# LF_HF_ant.net
KiCad netlist of a schematic drawn in EAGLE
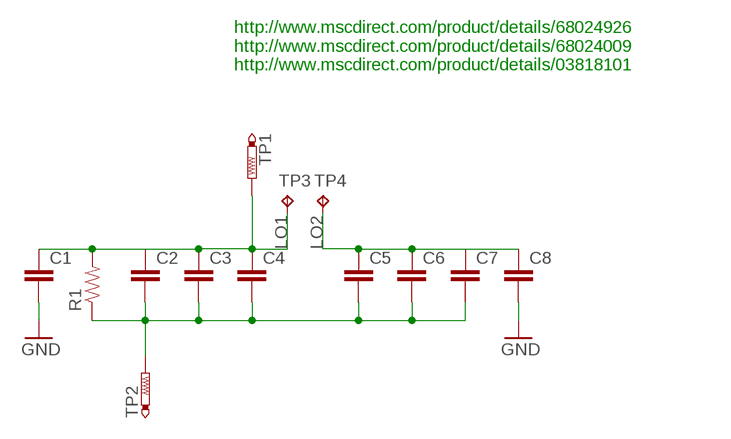
[diagram p0: schematic, sheet 1]
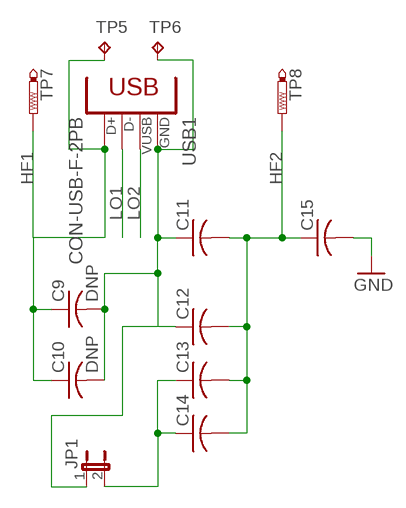
[diagram p1: schematic, sheet 2]

(export (version "E")
  (design (tool "Eeschema 10.0.6"))
  (components
    (comp (ref "C9")
      (value "DNP")
      (footprint "eagle-import:C1206")
      (libsource (lib "eagle-import") (part "C-USC1206"))
    )
    (comp (ref "C10")
      (value "DNP")
      (footprint "eagle-import:C1206")
      (libsource (lib "eagle-import") (part "C-USC1206"))
    )
    (comp (ref "C11")
      (value "C-USC1206")
      (footprint "eagle-import:C1206")
      (libsource (lib "eagle-import") (part "C-USC1206"))
    )
    (comp (ref "C12")
      (value "C-USC1206")
      (footprint "eagle-import:C1206")
      (libsource (lib "eagle-import") (part "C-USC1206"))
    )
    (comp (ref "C13")
      (value "C-USC1206")
      (footprint "eagle-import:C1206")
      (libsource (lib "eagle-import") (part "C-USC1206"))
    )
    (comp (ref "C14")
      (value "C-USC1206")
      (footprint "eagle-import:C1206")
      (libsource (lib "eagle-import") (part "C-USC1206"))
    )
    (comp (ref "C15")
      (value "C-USC1206")
      (footprint "eagle-import:C1206")
      (libsource (lib "eagle-import") (part "C-USC1206"))
    )
    (comp (ref "JP1")
      (value "JUMPER-2SMD-NO")
      (footprint "eagle-import:SJ_2S-NO")
      (libsource (lib "eagle-import") (part "JUMPER-2SMD-NO"))
    )
    (comp (ref "TP5")
      (value "TP")
      (footprint "eagle-import:TP_MILLMAX_R")
      (libsource (lib "eagle-import") (part "TP"))
    )
    (comp (ref "TP6")
      (value "TP")
      (footprint "eagle-import:TP_MILLMAX_R")
      (libsource (lib "eagle-import") (part "TP"))
    )
    (comp (ref "TP7")
      (value "PTR1PAD1-17")
      (footprint "eagle-import:P1-17")
      (libsource (lib "eagle-import") (part "PTR1PAD1-17"))
    )
    (comp (ref "TP8")
      (value "PTR1PAD1-17")
      (footprint "eagle-import:P1-17")
      (libsource (lib "eagle-import") (part "PTR1PAD1-17"))
    )
    (comp (ref "USB1")
      (value "CON-USB-F-2PB")
      (footprint "eagle-import:CONN_USB_A_F")
      (libsource (lib "eagle-import") (part "CON-USB-F-2PB"))
    )
    (comp (ref "C1")
      (value "CAP1206")
      (footprint "eagle-import:1206")
      (libsource (lib "eagle-import") (part "CAP1206"))
    )
    (comp (ref "C2")
      (value "CAP1206")
      (footprint "eagle-import:1206")
      (libsource (lib "eagle-import") (part "CAP1206"))
    )
    (comp (ref "C3")
      (value "CAP1206")
      (footprint "eagle-import:1206")
      (libsource (lib "eagle-import") (part "CAP1206"))
    )
    (comp (ref "C4")
      (value "CAP1206")
      (footprint "eagle-import:1206")
      (libsource (lib "eagle-import") (part "CAP1206"))
    )
    (comp (ref "C5")
      (value "CAP1206")
      (footprint "eagle-import:1206")
      (libsource (lib "eagle-import") (part "CAP1206"))
    )
    (comp (ref "C6")
      (value "CAP1206")
      (footprint "eagle-import:1206")
      (libsource (lib "eagle-import") (part "CAP1206"))
    )
    (comp (ref "C7")
      (value "CAP1206")
      (footprint "eagle-import:1206")
      (libsource (lib "eagle-import") (part "CAP1206"))
    )
    (comp (ref "C8")
      (value "CAP1206")
      (footprint "eagle-import:1206")
      (libsource (lib "eagle-import") (part "CAP1206"))
    )
    (comp (ref "R1")
      (value "RESISTOR0603-RES")
      (footprint "eagle-import:0603-RES")
      (libsource (lib "eagle-import") (part "RESISTOR0603-RES"))
    )
    (comp (ref "TP1")
      (value "PTR1PAD1-17")
      (footprint "eagle-import:P1-17")
      (libsource (lib "eagle-import") (part "PTR1PAD1-17"))
    )
    (comp (ref "TP2")
      (value "PTR1PAD1-17")
      (footprint "eagle-import:P1-17")
      (libsource (lib "eagle-import") (part "PTR1PAD1-17"))
    )
    (comp (ref "TP3")
      (value "TP")
      (footprint "eagle-import:TP_MILLMAX_R")
      (libsource (lib "eagle-import") (part "TP"))
    )
    (comp (ref "TP4")
      (value "TP")
      (footprint "eagle-import:TP_MILLMAX_R")
      (libsource (lib "eagle-import") (part "TP"))
    )
  )
  (nets
    (net (code "1") (name "GND") (class "Default")
      (node (ref "C1") (pin "2") (pinfunction "2_2") (pintype "passive"))
      (node (ref "C15") (pin "2") (pinfunction "2_2") (pintype "passive"))
      (node (ref "C8") (pin "2") (pinfunction "2_2") (pintype "passive"))
    )
    (net (code "2") (name "HF1") (class "Default")
      (node (ref "C10") (pin "1") (pinfunction "1_1") (pintype "passive"))
      (node (ref "C9") (pin "1") (pinfunction "1_1") (pintype "passive"))
      (node (ref "TP5") (pin "TP") (pinfunction "TP_TP") (pintype "input"))
      (node (ref "TP7") (pin "TP") (pinfunction "TP_TP") (pintype "input"))
      (node (ref "USB1") (pin "3") (pinfunction "D+_3") (pintype "bidirectional"))
    )
    (net (code "3") (name "HF2") (class "Default")
      (node (ref "C11") (pin "2") (pinfunction "2_2") (pintype "passive"))
      (node (ref "C12") (pin "2") (pinfunction "2_2") (pintype "passive"))
      (node (ref "C13") (pin "2") (pinfunction "2_2") (pintype "passive"))
      (node (ref "C14") (pin "2") (pinfunction "2_2") (pintype "passive"))
      (node (ref "C15") (pin "1") (pinfunction "1_1") (pintype "passive"))
      (node (ref "TP8") (pin "TP") (pinfunction "TP_TP") (pintype "input"))
    )
    (net (code "4") (name "LO1") (class "Default")
      (node (ref "C1") (pin "1") (pinfunction "1_1") (pintype "passive"))
      (node (ref "C2") (pin "1") (pinfunction "1_1") (pintype "passive"))
      (node (ref "C3") (pin "1") (pinfunction "1_1") (pintype "passive"))
      (node (ref "C4") (pin "1") (pinfunction "1_1") (pintype "passive"))
      (node (ref "R1") (pin "2") (pinfunction "2_2") (pintype "passive"))
      (node (ref "TP1") (pin "TP") (pinfunction "TP_TP") (pintype "input"))
      (node (ref "TP3") (pin "TP") (pinfunction "TP_TP") (pintype "input"))
      (node (ref "USB1") (pin "2") (pinfunction "D-_2") (pintype "bidirectional"))
    )
    (net (code "5") (name "LO2") (class "Default")
      (node (ref "C5") (pin "1") (pinfunction "1_1") (pintype "passive"))
      (node (ref "C6") (pin "1") (pinfunction "1_1") (pintype "passive"))
      (node (ref "C7") (pin "1") (pinfunction "1_1") (pintype "passive"))
      (node (ref "C8") (pin "1") (pinfunction "1_1") (pintype "passive"))
      (node (ref "TP4") (pin "TP") (pinfunction "TP_TP") (pintype "input"))
      (node (ref "USB1") (pin "1") (pinfunction "VUSB_1") (pintype "bidirectional"))
    )
    (net (code "6") (name "Net-(C2-Pad2)") (class "Default")
      (node (ref "C2") (pin "2") (pinfunction "2_2") (pintype "passive"))
      (node (ref "C3") (pin "2") (pinfunction "2_2") (pintype "passive"))
      (node (ref "C4") (pin "2") (pinfunction "2_2") (pintype "passive"))
      (node (ref "C5") (pin "2") (pinfunction "2_2") (pintype "passive"))
      (node (ref "C6") (pin "2") (pinfunction "2_2") (pintype "passive"))
      (node (ref "C7") (pin "2") (pinfunction "2_2") (pintype "passive"))
      (node (ref "R1") (pin "1") (pinfunction "1_1") (pintype "passive"))
      (node (ref "TP2") (pin "TP") (pinfunction "TP_TP") (pintype "input"))
    )
    (net (code "7") (name "Net-(C13-Pad1)") (class "Default")
      (node (ref "C13") (pin "1") (pinfunction "1_1") (pintype "passive"))
      (node (ref "C14") (pin "1") (pinfunction "1_1") (pintype "passive"))
      (node (ref "JP1") (pin "2") (pinfunction "2_2") (pintype "passive"))
    )
    (net (code "8") (name "Net-(USB1B-GND)") (class "Default")
      (node (ref "C10") (pin "2") (pinfunction "2_2") (pintype "passive"))
      (node (ref "C11") (pin "1") (pinfunction "1_1") (pintype "passive"))
      (node (ref "C12") (pin "1") (pinfunction "1_1") (pintype "passive"))
      (node (ref "C9") (pin "2") (pinfunction "2_2") (pintype "passive"))
      (node (ref "JP1") (pin "1") (pinfunction "1_1") (pintype "passive"))
      (node (ref "TP6") (pin "TP") (pinfunction "TP_TP") (pintype "input"))
      (node (ref "USB1") (pin "4") (pinfunction "GND_4") (pintype "bidirectional"))
    )
  )
)
